# boarthed_to.net
KiCad netlist of a schematic drawn in EAGLE
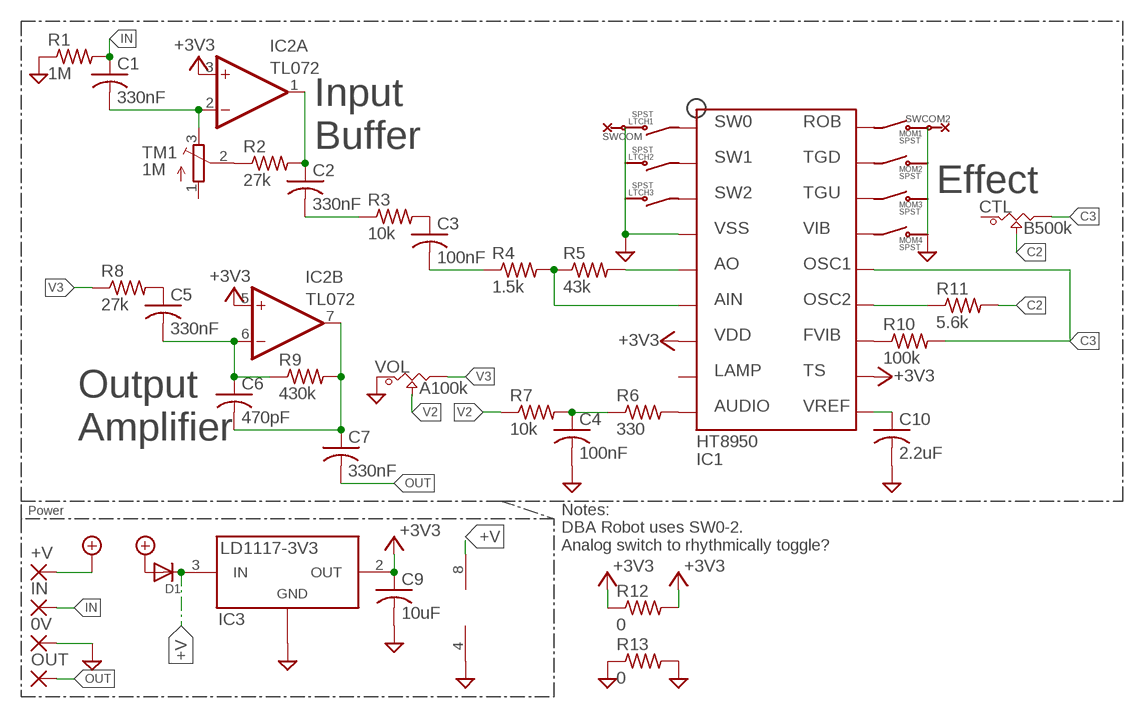
[diagram p0: schematic, sheet 1]

(export (version "E")
  (design (tool "Eeschema 10.0.6"))
  (components
    (comp (ref "+V")
      (value "SMD2")
      (footprint "eagle-import:SMD1,27-2,54")
      (libsource (lib "eagle-import") (part "SMD2"))
    )
    (comp (ref "0V")
      (value "SMD2")
      (footprint "eagle-import:SMD1,27-2,54")
      (libsource (lib "eagle-import") (part "SMD2"))
    )
    (comp (ref "C1")
      (value "330nF")
      (footprint "eagle-import:C0603")
      (libsource (lib "eagle-import") (part "C-USC0603"))
    )
    (comp (ref "C2")
      (value "330nF")
      (footprint "eagle-import:C0603")
      (libsource (lib "eagle-import") (part "C-USC0603"))
    )
    (comp (ref "C3")
      (value "100nF")
      (footprint "eagle-import:C0603")
      (libsource (lib "eagle-import") (part "C-USC0603"))
    )
    (comp (ref "C4")
      (value "100nF")
      (footprint "eagle-import:C0603")
      (libsource (lib "eagle-import") (part "C-USC0603"))
    )
    (comp (ref "C5")
      (value "330nF")
      (footprint "eagle-import:C0603")
      (libsource (lib "eagle-import") (part "C-USC0603"))
    )
    (comp (ref "C6")
      (value "470pF")
      (footprint "eagle-import:C0603")
      (libsource (lib "eagle-import") (part "C-USC0603"))
    )
    (comp (ref "C7")
      (value "330nF")
      (footprint "eagle-import:C0603")
      (libsource (lib "eagle-import") (part "C-USC0603"))
    )
    (comp (ref "C9")
      (value "10uF")
      (footprint "eagle-import:C1206")
      (libsource (lib "eagle-import") (part "C-USC1206"))
    )
    (comp (ref "C10")
      (value "2.2uF")
      (footprint "eagle-import:C0603")
      (libsource (lib "eagle-import") (part "C-USC0603"))
    )
    (comp (ref "CTL")
      (value "B500k")
      (footprint "eagle-import:POT_9MM_SMD")
      (libsource (lib "eagle-import") (part "POT_9MM_SMD"))
    )
    (comp (ref "D1")
      (value "DIODESOD-123")
      (footprint "eagle-import:SOD-123")
      (libsource (lib "eagle-import") (part "DIODESOD-123"))
    )
    (comp (ref "IC2")
      (value "TL072")
      (footprint "eagle-import:TSSOP-8")
      (libsource (lib "eagle-import") (part "TL072TSSOP"))
    )
    (comp (ref "IC3")
      (value "LD1117-3V3")
      (footprint "eagle-import:SOT-223")
      (fields
        (field (name "DIGIKEY_PART_NUMBER") "497-1242-2-ND")
        (field (name "MANUFACTURER") "STMicroelectronics")
        (field (name "MPN") "LD1117S33TR")
        (field (name "CREATED_BY") "PCBLayout.com")
      )
      (libsource (lib "eagle-import") (part "LD1117S33TR"))
    )
    (comp (ref "IN")
      (value "SMD2")
      (footprint "eagle-import:SMD1,27-2,54")
      (libsource (lib "eagle-import") (part "SMD2"))
    )
    (comp (ref "LTCH1")
      (value "SPST_1PAD")
      (footprint "eagle-import:1PAD")
      (libsource (lib "eagle-import") (part "SPST_1PAD"))
    )
    (comp (ref "LTCH2")
      (value "SPST_1PAD")
      (footprint "eagle-import:1PAD")
      (libsource (lib "eagle-import") (part "SPST_1PAD"))
    )
    (comp (ref "LTCH3")
      (value "SPST_1PAD")
      (footprint "eagle-import:1PAD")
      (libsource (lib "eagle-import") (part "SPST_1PAD"))
    )
    (comp (ref "MOM1")
      (value "SPST_1PAD")
      (footprint "eagle-import:1PAD")
      (libsource (lib "eagle-import") (part "SPST_1PAD"))
    )
    (comp (ref "MOM2")
      (value "SPST_1PAD")
      (footprint "eagle-import:1PAD")
      (libsource (lib "eagle-import") (part "SPST_1PAD"))
    )
    (comp (ref "MOM3")
      (value "SPST_1PAD")
      (footprint "eagle-import:1PAD")
      (libsource (lib "eagle-import") (part "SPST_1PAD"))
    )
    (comp (ref "MOM4")
      (value "SPST_1PAD")
      (footprint "eagle-import:1PAD")
      (libsource (lib "eagle-import") (part "SPST_1PAD"))
    )
    (comp (ref "OUT")
      (value "SMD2")
      (footprint "eagle-import:SMD1,27-2,54")
      (libsource (lib "eagle-import") (part "SMD2"))
    )
    (comp (ref "R1")
      (value "1M")
      (footprint "eagle-import:R0603")
      (libsource (lib "eagle-import") (part "R-US_R0603"))
    )
    (comp (ref "R2")
      (value "27k")
      (footprint "eagle-import:R0603")
      (libsource (lib "eagle-import") (part "R-US_R0603"))
    )
    (comp (ref "R3")
      (value "10k")
      (footprint "eagle-import:R0603")
      (libsource (lib "eagle-import") (part "R-US_R0603"))
    )
    (comp (ref "R4")
      (value "1.5k")
      (footprint "eagle-import:R0603")
      (libsource (lib "eagle-import") (part "R-US_R0603"))
    )
    (comp (ref "R5")
      (value "43k")
      (footprint "eagle-import:R0603")
      (libsource (lib "eagle-import") (part "R-US_R0603"))
    )
    (comp (ref "R6")
      (value "330")
      (footprint "eagle-import:R0603")
      (libsource (lib "eagle-import") (part "R-US_R0603"))
    )
    (comp (ref "R7")
      (value "10k")
      (footprint "eagle-import:R0603")
      (libsource (lib "eagle-import") (part "R-US_R0603"))
    )
    (comp (ref "R8")
      (value "27k")
      (footprint "eagle-import:R0603")
      (libsource (lib "eagle-import") (part "R-US_R0603"))
    )
    (comp (ref "R9")
      (value "430k")
      (footprint "eagle-import:R0603")
      (libsource (lib "eagle-import") (part "R-US_R0603"))
    )
    (comp (ref "R10")
      (value "100k")
      (footprint "eagle-import:R0603")
      (libsource (lib "eagle-import") (part "R-US_R0603"))
    )
    (comp (ref "R11")
      (value "5.6k")
      (footprint "eagle-import:R0603")
      (libsource (lib "eagle-import") (part "R-US_R0603"))
    )
    (comp (ref "R12")
      (value "0")
      (footprint "eagle-import:R0402")
      (libsource (lib "eagle-import") (part "R-US_R0402"))
    )
    (comp (ref "R13")
      (value "0")
      (footprint "eagle-import:R0402")
      (libsource (lib "eagle-import") (part "R-US_R0402"))
    )
    (comp (ref "SWCOM")
      (value "COM_SMD")
      (footprint "eagle-import:1PAD")
      (libsource (lib "eagle-import") (part "COM_SMD"))
    )
    (comp (ref "SWCOM2")
      (value "COM_SMD")
      (footprint "eagle-import:1PAD")
      (libsource (lib "eagle-import") (part "COM_SMD"))
    )
    (comp (ref "TM1")
      (value "1M")
      (footprint "eagle-import:TC33X")
      (libsource (lib "eagle-import") (part "TRIMPOTTC33X"))
    )
    (comp (ref "U$4")
      (value "HT8950")
      (footprint "eagle-import:PDIP-18")
      (libsource (lib "eagle-import") (part "HT8950"))
    )
    (comp (ref "VOL")
      (value "A100k")
      (footprint "eagle-import:POT_9MM_SMD")
      (libsource (lib "eagle-import") (part "POT_9MM_SMD"))
    )
  )
  (nets
    (net (code "1") (name "+3V3") (class "Default")
      (node (ref "C9") (pin "1") (pinfunction "1_1") (pintype "passive"))
      (node (ref "IC2") (pin "3") (pinfunction "+IN_3") (pintype "input"))
      (node (ref "IC2") (pin "5") (pinfunction "+IN_5") (pintype "input"))
      (node (ref "IC3") (pin "2") (pinfunction "OUT_2") (pintype "output"))
      (node (ref "IC3") (pin "4") (pinfunction "4_4") (pintype "passive"))
      (node (ref "R12") (pin "1") (pinfunction "1_1") (pintype "passive"))
      (node (ref "R12") (pin "2") (pinfunction "2_2") (pintype "passive"))
      (node (ref "U$4") (pin "11") (pinfunction "TS_11") (pintype "bidirectional"))
      (node (ref "U$4") (pin "7") (pinfunction "VDD_7") (pintype "bidirectional"))
    )
    (net (code "2") (name "+9V") (class "Default")
      (node (ref "+V") (pin "1") (pinfunction "P_1") (pintype "passive"))
      (node (ref "D1") (pin "A") (pinfunction "A_A") (pintype "passive"))
    )
    (net (code "3") (name "+V") (class "Default")
      (node (ref "D1") (pin "C") (pinfunction "C_C") (pintype "passive"))
      (node (ref "IC2") (pin "8") (pinfunction "V+_8") (pintype "power_in"))
      (node (ref "IC3") (pin "3") (pinfunction "IN_3") (pintype "input"))
    )
    (net (code "4") (name "C2") (class "Default")
      (node (ref "CTL") (pin "2") (pinfunction "2_2") (pintype "bidirectional"))
      (node (ref "R11") (pin "2") (pinfunction "2_2") (pintype "passive"))
    )
    (net (code "5") (name "C3") (class "Default")
      (node (ref "CTL") (pin "3") (pinfunction "3_3") (pintype "bidirectional"))
      (node (ref "R10") (pin "2") (pinfunction "2_2") (pintype "passive"))
      (node (ref "U$4") (pin "14") (pinfunction "OSC1_14") (pintype "bidirectional"))
    )
    (net (code "6") (name "GND") (class "Default")
      (node (ref "0V") (pin "1") (pinfunction "P_1") (pintype "passive"))
      (node (ref "C10") (pin "2") (pinfunction "2_2") (pintype "passive"))
      (node (ref "C4") (pin "2") (pinfunction "2_2") (pintype "passive"))
      (node (ref "C9") (pin "2") (pinfunction "2_2") (pintype "passive"))
      (node (ref "IC2") (pin "4") (pinfunction "V-_4") (pintype "power_in"))
      (node (ref "IC3") (pin "1") (pinfunction "ADJ/GND_1") (pintype "power_in"))
      (node (ref "R1") (pin "1") (pinfunction "1_1") (pintype "passive"))
      (node (ref "R13") (pin "1") (pinfunction "1_1") (pintype "passive"))
      (node (ref "R13") (pin "2") (pinfunction "2_2") (pintype "passive"))
      (node (ref "SWCOM") (pin "1") (pinfunction "1_1") (pintype "bidirectional"))
      (node (ref "SWCOM2") (pin "1") (pinfunction "1_1") (pintype "bidirectional"))
      (node (ref "U$4") (pin "4") (pinfunction "VSS_4") (pintype "bidirectional"))
      (node (ref "VOL") (pin "1") (pinfunction "1_1") (pintype "bidirectional"))
    )
    (net (code "7") (name "IN") (class "Default")
      (node (ref "C1") (pin "1") (pinfunction "1_1") (pintype "passive"))
      (node (ref "IN") (pin "1") (pinfunction "P_1") (pintype "passive"))
      (node (ref "R1") (pin "2") (pinfunction "2_2") (pintype "passive"))
    )
    (net (code "8") (name "Net-(C2-Pad2)") (class "Default")
      (node (ref "C2") (pin "2") (pinfunction "2_2") (pintype "passive"))
      (node (ref "R3") (pin "1") (pinfunction "1_1") (pintype "passive"))
    )
    (net (code "9") (name "Net-(C3-Pad1)") (class "Default")
      (node (ref "C3") (pin "1") (pinfunction "1_1") (pintype "passive"))
      (node (ref "R3") (pin "2") (pinfunction "2_2") (pintype "passive"))
    )
    (net (code "10") (name "Net-(C3-Pad2)") (class "Default")
      (node (ref "C3") (pin "2") (pinfunction "2_2") (pintype "passive"))
      (node (ref "R4") (pin "1") (pinfunction "1_1") (pintype "passive"))
    )
    (net (code "11") (name "Net-(C4-Pad1)") (class "Default")
      (node (ref "C4") (pin "1") (pinfunction "1_1") (pintype "passive"))
      (node (ref "R6") (pin "1") (pinfunction "1_1") (pintype "passive"))
      (node (ref "R7") (pin "2") (pinfunction "2_2") (pintype "passive"))
    )
    (net (code "12") (name "Net-(C5-Pad1)") (class "Default")
      (node (ref "C5") (pin "1") (pinfunction "1_1") (pintype "passive"))
      (node (ref "R8") (pin "2") (pinfunction "2_2") (pintype "passive"))
    )
    (net (code "13") (name "Net-(IC2A--IN)") (class "Default")
      (node (ref "C1") (pin "2") (pinfunction "2_2") (pintype "passive"))
      (node (ref "IC2") (pin "2") (pinfunction "-IN_2") (pintype "input"))
      (node (ref "TM1") (pin "3") (pinfunction "E_3") (pintype "passive"))
    )
    (net (code "14") (name "Net-(IC2A-OUT)") (class "Default")
      (node (ref "C2") (pin "1") (pinfunction "1_1") (pintype "passive"))
      (node (ref "IC2") (pin "1") (pinfunction "OUT_1") (pintype "output"))
      (node (ref "R2") (pin "2") (pinfunction "2_2") (pintype "passive"))
    )
    (net (code "15") (name "Net-(IC2B--IN)") (class "Default")
      (node (ref "C5") (pin "2") (pinfunction "2_2") (pintype "passive"))
      (node (ref "C6") (pin "1") (pinfunction "1_1") (pintype "passive"))
      (node (ref "IC2") (pin "6") (pinfunction "-IN_6") (pintype "input"))
      (node (ref "R9") (pin "1") (pinfunction "1_1") (pintype "passive"))
    )
    (net (code "16") (name "Net-(IC2B-OUT)") (class "Default")
      (node (ref "C6") (pin "2") (pinfunction "2_2") (pintype "passive"))
      (node (ref "C7") (pin "1") (pinfunction "1_1") (pintype "passive"))
      (node (ref "IC2") (pin "7") (pinfunction "OUT_7") (pintype "output"))
      (node (ref "R9") (pin "2") (pinfunction "2_2") (pintype "passive"))
    )
    (net (code "17") (name "Net-(TM1-S)") (class "Default")
      (node (ref "R2") (pin "1") (pinfunction "1_1") (pintype "passive"))
      (node (ref "TM1") (pin "2") (pinfunction "S_2") (pintype "passive"))
    )
    (net (code "18") (name "Net-(U$4-AIN)") (class "Default")
      (node (ref "R4") (pin "2") (pinfunction "2_2") (pintype "passive"))
      (node (ref "R5") (pin "1") (pinfunction "1_1") (pintype "passive"))
      (node (ref "U$4") (pin "6") (pinfunction "AIN_6") (pintype "bidirectional"))
    )
    (net (code "19") (name "Net-(U$4-AO)") (class "Default")
      (node (ref "R5") (pin "2") (pinfunction "2_2") (pintype "passive"))
      (node (ref "U$4") (pin "5") (pinfunction "AO_5") (pintype "bidirectional"))
    )
    (net (code "20") (name "Net-(U$4-AUDIO)") (class "Default")
      (node (ref "R6") (pin "2") (pinfunction "2_2") (pintype "passive"))
      (node (ref "U$4") (pin "9") (pinfunction "AUDIO_9") (pintype "bidirectional"))
    )
    (net (code "21") (name "Net-(U$4-FVIB)") (class "Default")
      (node (ref "R10") (pin "1") (pinfunction "1_1") (pintype "passive"))
      (node (ref "U$4") (pin "12") (pinfunction "FVIB_12") (pintype "bidirectional"))
    )
    (net (code "22") (name "Net-(U$4-OSC2)") (class "Default")
      (node (ref "R11") (pin "1") (pinfunction "1_1") (pintype "passive"))
      (node (ref "U$4") (pin "13") (pinfunction "OSC2_13") (pintype "bidirectional"))
    )
    (net (code "23") (name "Net-(U$4-ROB)") (class "Default")
      (node (ref "MOM1") (pin "1") (pinfunction "1_1") (pintype "bidirectional"))
      (node (ref "U$4") (pin "18") (pinfunction "ROB_18") (pintype "bidirectional"))
    )
    (net (code "24") (name "Net-(U$4-SW0)") (class "Default")
      (node (ref "LTCH1") (pin "1") (pinfunction "1_1") (pintype "bidirectional"))
      (node (ref "U$4") (pin "1") (pinfunction "SW0_1") (pintype "bidirectional"))
    )
    (net (code "25") (name "Net-(U$4-SW1)") (class "Default")
      (node (ref "LTCH2") (pin "1") (pinfunction "1_1") (pintype "bidirectional"))
      (node (ref "U$4") (pin "2") (pinfunction "SW1_2") (pintype "bidirectional"))
    )
    (net (code "26") (name "Net-(U$4-SW2)") (class "Default")
      (node (ref "LTCH3") (pin "1") (pinfunction "1_1") (pintype "bidirectional"))
      (node (ref "U$4") (pin "3") (pinfunction "SW2_3") (pintype "bidirectional"))
    )
    (net (code "27") (name "Net-(U$4-TGD)") (class "Default")
      (node (ref "MOM2") (pin "1") (pinfunction "1_1") (pintype "bidirectional"))
      (node (ref "U$4") (pin "17") (pinfunction "TGD_17") (pintype "bidirectional"))
    )
    (net (code "28") (name "Net-(U$4-TGU)") (class "Default")
      (node (ref "MOM3") (pin "1") (pinfunction "1_1") (pintype "bidirectional"))
      (node (ref "U$4") (pin "16") (pinfunction "TGU_16") (pintype "bidirectional"))
    )
    (net (code "29") (name "Net-(U$4-VIB)") (class "Default")
      (node (ref "MOM4") (pin "1") (pinfunction "1_1") (pintype "bidirectional"))
      (node (ref "U$4") (pin "15") (pinfunction "VIB_15") (pintype "bidirectional"))
    )
    (net (code "30") (name "Net-(U$4-VREF)") (class "Default")
      (node (ref "C10") (pin "1") (pinfunction "1_1") (pintype "passive"))
      (node (ref "U$4") (pin "10") (pinfunction "VREF_10") (pintype "bidirectional"))
    )
    (net (code "31") (name "OUT") (class "Default")
      (node (ref "C7") (pin "2") (pinfunction "2_2") (pintype "passive"))
      (node (ref "OUT") (pin "1") (pinfunction "P_1") (pintype "passive"))
    )
    (net (code "32") (name "V2") (class "Default")
      (node (ref "R7") (pin "1") (pinfunction "1_1") (pintype "passive"))
      (node (ref "VOL") (pin "2") (pinfunction "2_2") (pintype "bidirectional"))
    )
    (net (code "33") (name "V3") (class "Default")
      (node (ref "R8") (pin "1") (pinfunction "1_1") (pintype "passive"))
      (node (ref "VOL") (pin "3") (pinfunction "3_3") (pintype "bidirectional"))
    )
    (net (code "34") (name "unconnected-(CTL-Pad1)") (class "Default")
      (node (ref "CTL") (pin "1") (pinfunction "1_1") (pintype "bidirectional"))
    )
    (net (code "35") (name "unconnected-(TM1-A-Pad1)") (class "Default")
      (node (ref "TM1") (pin "1") (pinfunction "A_1") (pintype "passive"))
    )
    (net (code "36") (name "unconnected-(U$4-LAMP-Pad8)") (class "Default")
      (node (ref "U$4") (pin "8") (pinfunction "LAMP_8") (pintype "bidirectional"))
    )
  )
)
